# Controlador_USB_Maestro.net
KiCad netlist of a schematic drawn in Altium Designer
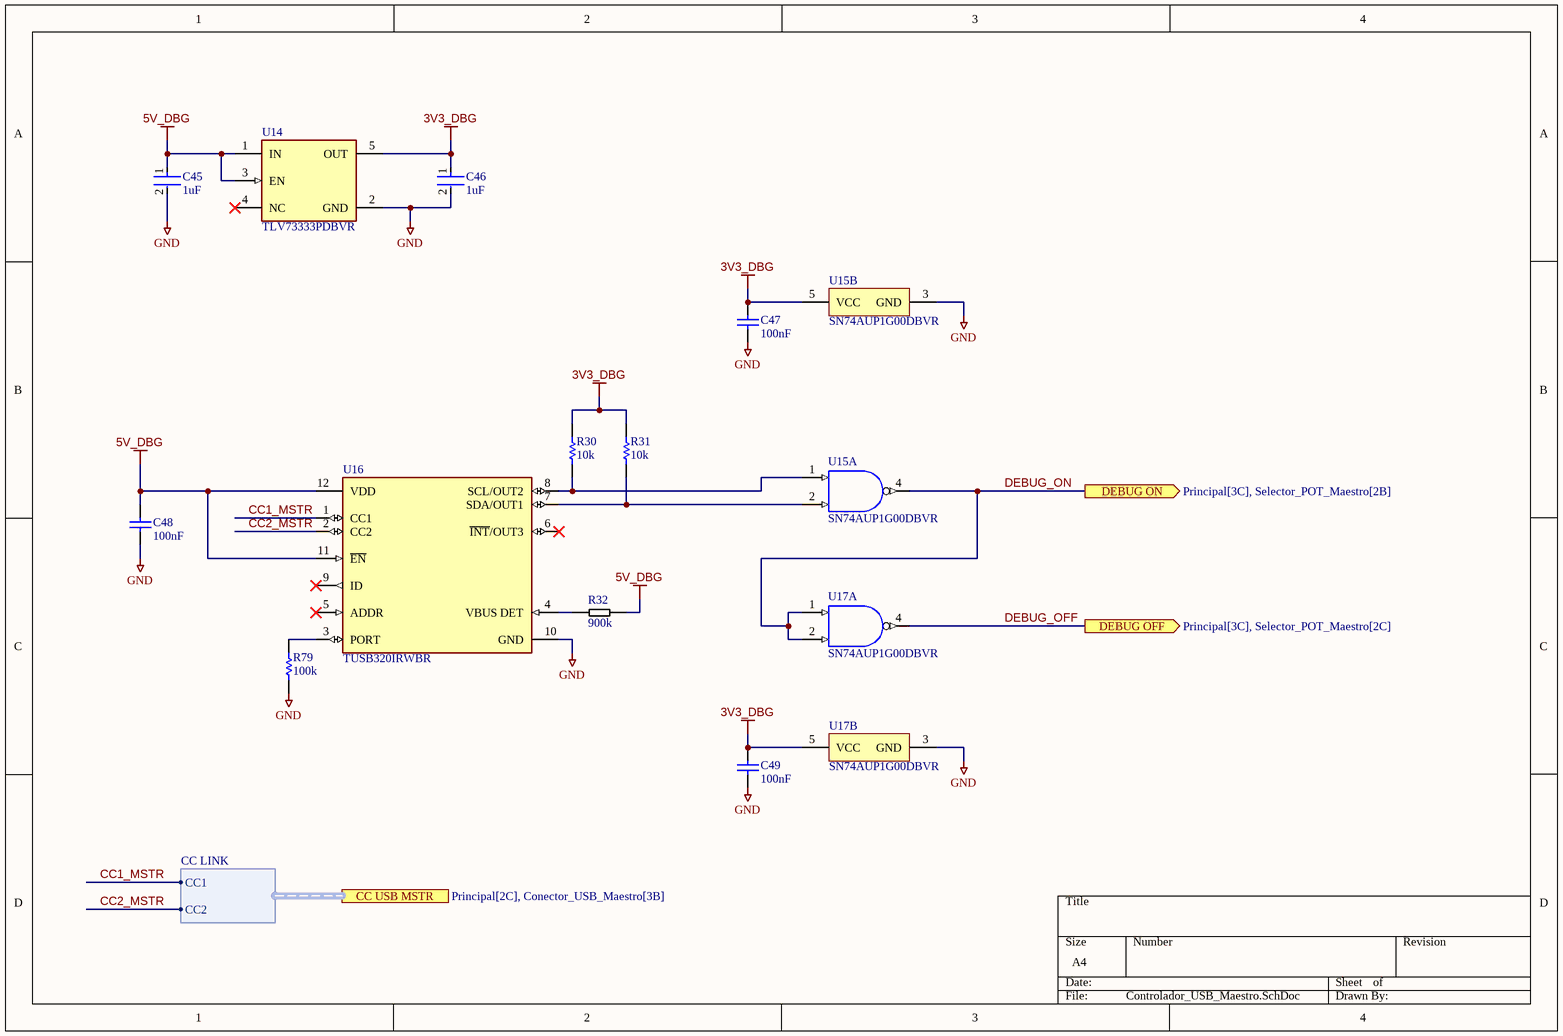
[diagram p0: Controlador_USB_Maestro.SchDoc]

(export (version "E")
  (design (tool "Eeschema 10.0.6"))
  (components
    (comp (ref "C45")
      (value "1uF")
      (footprint "FP-C0402C-BB-IPC_B")
      (description "CAP CER 1UF 16V X5R 0402")
      (fields (field (name "TOLERANCE") "10%"))
      (libsource (lib "Altium Content Vault") (part "b4654b650e69147ec39a6b967a45e02"))
    )
    (comp (ref "C46")
      (value "1uF")
      (footprint "FP-C0402C-BB-IPC_B")
      (description "CAP CER 1UF 16V X5R 0402")
      (fields (field (name "TOLERANCE") "10%"))
      (libsource (lib "Altium Content Vault") (part "b4654b650e69147ec39a6b967a45e02"))
    )
    (comp (ref "C47")
      (value "100nF")
      (footprint "CAPC1005X55X25NL05T05")
      (fields (field (name "MANUFACTURER") "Vitramon") (field (name "PART NUMBER") "VJ0402Y104KXJCW1BC"))
      (libsource (lib "Altium Content Vault") (part "CAP"))
    )
    (comp (ref "C48")
      (value "100nF")
      (footprint "CAPC1005X55X25NL05T05")
      (fields (field (name "MANUFACTURER") "Vitramon") (field (name "PART NUMBER") "VJ0402Y104KXJCW1BC"))
      (libsource (lib "Altium Content Vault") (part "CAP"))
    )
    (comp (ref "C49")
      (value "100nF")
      (footprint "CAPC1005X55X25NL05T05")
      (fields (field (name "MANUFACTURER") "Vitramon") (field (name "PART NUMBER") "VJ0402Y104KXJCW1BC"))
      (libsource (lib "Altium Content Vault") (part "CAP"))
    )
    (comp (ref "R30")
      (value "10k")
      (footprint "RESC1005X40X25NL05T05")
      (fields (field (name "MANUFACTURER") "Panasonic") (field (name "PART NUMBER") "ERJ-2RHD1002X"))
      (libsource (lib "Altium Content Vault") (part "RES"))
    )
    (comp (ref "R31")
      (value "10k")
      (footprint "RESC1005X40X25NL05T05")
      (fields (field (name "MANUFACTURER") "Panasonic") (field (name "PART NUMBER") "ERJ-2RHD1002X"))
      (libsource (lib "Altium Content Vault") (part "RES"))
    )
    (comp (ref "R32")
      (value "900k")
      (footprint "RES 1206")
      (description "900k Resistor 200V 1206 0.5%")
      (libsource (lib "Esquemas") (part "RT1206CRE07900KL"))
    )
    (comp (ref "R79")
      (value "100k")
      (footprint "RESC1005X40X25ML10T10")
      (fields (field (name "PART NUMBER") "SG73P1ETTP1003F") (field (name "MANUFACTURER") "KOA Speer"))
      (libsource (lib "Altium Content Vault") (part "RES"))
    )
    (comp (ref "U14")
      (value "TLV73333PDBVR")
      (footprint "FP-DBV0005A-MFG")
      (description "IC REG LINEAR 3.3V 300MA SOT23-5")
      (fields
        (field (name "MANUFACTURER") "Texas Instruments")
        (field (name "OCTOPART") "https://octopart.com/tlv73333pdbvr-texas+instruments-51080890")
      )
      (libsource (lib "Altium Content Vault") (part "10cdd6a861ce8db355dac0efc8b397e"))
    )
    (comp (ref "U15")
      (value "SN74AUP1G00DBVR")
      (footprint "DBV0005A_N")
      (description "Low-Power Single Two-Input Positive-NAND Gate, DBV0005A, LARGE T&R")
      (fields
        (field (name "GENERIC PART NUMBER") "SN74AUP1G00")
        (field (name "MANUFACTURER") "Texas Instruments")
      )
      (libsource (lib "Altium Content Vault") (part "TI-SN74XXX1XXXX-5"))
    )
    (comp (ref "U16")
      (value "TUSB320IRWBR")
      (footprint "FP-RWB0012A-MFG")
      (description "IC INTERFACE SPECIALIZED 12X2QFN")
      (libsource (lib "Altium Content Vault") (part "76af6d7f95a64df20dc6dc148ef600c"))
    )
    (comp (ref "U17")
      (value "SN74AUP1G00DBVR")
      (footprint "DBV0005A_N")
      (description "Low-Power Single Two-Input Positive-NAND Gate, DBV0005A, LARGE T&R")
      (fields
        (field (name "GENERIC PART NUMBER") "SN74AUP1G00")
        (field (name "MANUFACTURER") "Texas Instruments")
      )
      (libsource (lib "Altium Content Vault") (part "TI-SN74XXX1XXXX-5"))
    )
  )
  (nets
    (net (code "3") (name "/CC1_MSTR") (class "Default")
      (node (ref "U16") (pin "1") (pinfunction "CC1_1") (pintype "bidirectional"))
    )
    (net (code "4") (name "/CC2_MSTR") (class "Default")
      (node (ref "U16") (pin "2") (pinfunction "CC2_2") (pintype "bidirectional"))
    )
    (net (code "5") (name "/DEBUG_OFF") (class "Default")
      (node (ref "U17") (pin "4") (pinfunction "Y_4") (pintype "output"))
    )
    (net (code "6") (name "/DEBUG_ON") (class "Default")
      (node (ref "U15") (pin "4") (pinfunction "Y_4") (pintype "output"))
      (node (ref "U17") (pin "1") (pinfunction "A_1") (pintype "input"))
      (node (ref "U17") (pin "2") (pinfunction "B_2") (pintype "input"))
    )
    (net (code "8") (name "3V3_DBG") (class "Default")
      (node (ref "C46") (pin "1") (pinfunction "1_1") (pintype "passive"))
      (node (ref "C47") (pin "2") (pinfunction "2_2") (pintype "passive"))
      (node (ref "C49") (pin "2") (pinfunction "2_2") (pintype "passive"))
      (node (ref "R30") (pin "2") (pinfunction "2_2") (pintype "passive"))
      (node (ref "R31") (pin "2") (pinfunction "2_2") (pintype "passive"))
      (node (ref "U14") (pin "5") (pinfunction "OUT_5") (pintype "power_in"))
      (node (ref "U15") (pin "5") (pinfunction "VCC_5") (pintype "power_in"))
      (node (ref "U17") (pin "5") (pinfunction "VCC_5") (pintype "power_in"))
    )
    (net (code "9") (name "5V_DBG") (class "Default")
      (node (ref "C45") (pin "1") (pinfunction "1_1") (pintype "passive"))
      (node (ref "C48") (pin "2") (pinfunction "2_2") (pintype "passive"))
      (node (ref "R32") (pin "1") (pintype "passive"))
      (node (ref "U14") (pin "1") (pinfunction "IN_1") (pintype "passive"))
      (node (ref "U14") (pin "3") (pinfunction "EN_3") (pintype "input"))
      (node (ref "U16") (pin "11") (pinfunction "~{EN}_11") (pintype "input"))
      (node (ref "U16") (pin "12") (pinfunction "VDD_12") (pintype "passive"))
    )
    (net (code "10") (name "GND") (class "Default")
      (node (ref "C45") (pin "2") (pinfunction "2_2") (pintype "passive"))
      (node (ref "C46") (pin "2") (pinfunction "2_2") (pintype "passive"))
      (node (ref "C47") (pin "1") (pinfunction "1_1") (pintype "passive"))
      (node (ref "C48") (pin "1") (pinfunction "1_1") (pintype "passive"))
      (node (ref "C49") (pin "1") (pinfunction "1_1") (pintype "passive"))
      (node (ref "R79") (pin "1") (pinfunction "1_1") (pintype "passive"))
      (node (ref "U14") (pin "2") (pinfunction "GND_2") (pintype "passive"))
      (node (ref "U15") (pin "3") (pinfunction "GND_3") (pintype "power_in"))
      (node (ref "U16") (pin "10") (pinfunction "GND_10") (pintype "passive"))
      (node (ref "U17") (pin "3") (pinfunction "GND_3") (pintype "power_in"))
    )
    (net (code "11") (name "Net-(U15A-A)") (class "Default")
      (node (ref "R30") (pin "1") (pinfunction "1_1") (pintype "passive"))
      (node (ref "U15") (pin "1") (pinfunction "A_1") (pintype "input"))
      (node (ref "U16") (pin "8") (pinfunction "SCL/OUT2_8") (pintype "bidirectional"))
    )
    (net (code "12") (name "Net-(U15A-B)") (class "Default")
      (node (ref "R31") (pin "1") (pinfunction "1_1") (pintype "passive"))
      (node (ref "U15") (pin "2") (pinfunction "B_2") (pintype "input"))
      (node (ref "U16") (pin "7") (pinfunction "SDA/OUT1_7") (pintype "bidirectional"))
    )
    (net (code "13") (name "Net-(U16-PORT)") (class "Default")
      (node (ref "R79") (pin "2") (pinfunction "2_2") (pintype "passive"))
      (node (ref "U16") (pin "3") (pinfunction "PORT_3") (pintype "bidirectional"))
    )
    (net (code "14") (name "Net-(U16-VBUS_DET)") (class "Default")
      (node (ref "R32") (pin "2") (pintype "passive"))
      (node (ref "U16") (pin "4") (pinfunction "VBUS_DET_4") (pintype "input"))
    )
    (net (code "15") (name "unconnected-(U14-NC-Pad4)") (class "Default")
      (node (ref "U14") (pin "4") (pinfunction "NC_4") (pintype "passive+no_connect"))
    )
    (net (code "16") (name "unconnected-(U16-ADDR-Pad5)") (class "Default")
      (node (ref "U16") (pin "5") (pinfunction "ADDR_5") (pintype "input+no_connect"))
    )
    (net (code "17") (name "unconnected-(U16-ID-Pad9)") (class "Default")
      (node (ref "U16") (pin "9") (pinfunction "ID_9") (pintype "output+no_connect"))
    )
    (net (code "18") (name "unconnected-(U16-~{INT}{slash}OUT3-Pad6)") (class "Default")
      (node (ref "U16") (pin "6") (pinfunction "~{INT}/OUT3_6") (pintype "bidirectional+no_connect"))
    )
  )
)
